# ADC_IN.net
KiCad netlist of a schematic drawn in Altium Designer
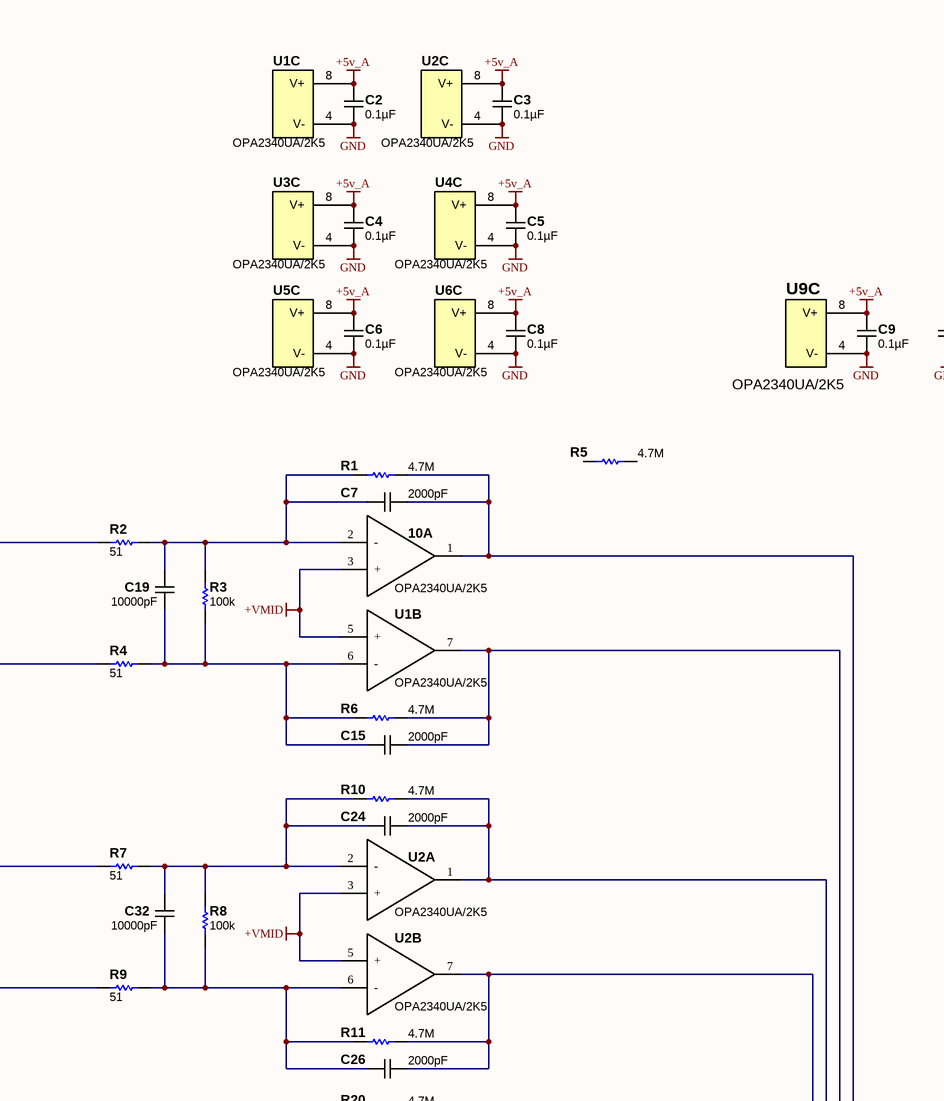
[diagram p0: ADC_IN.SchDoc, top left]
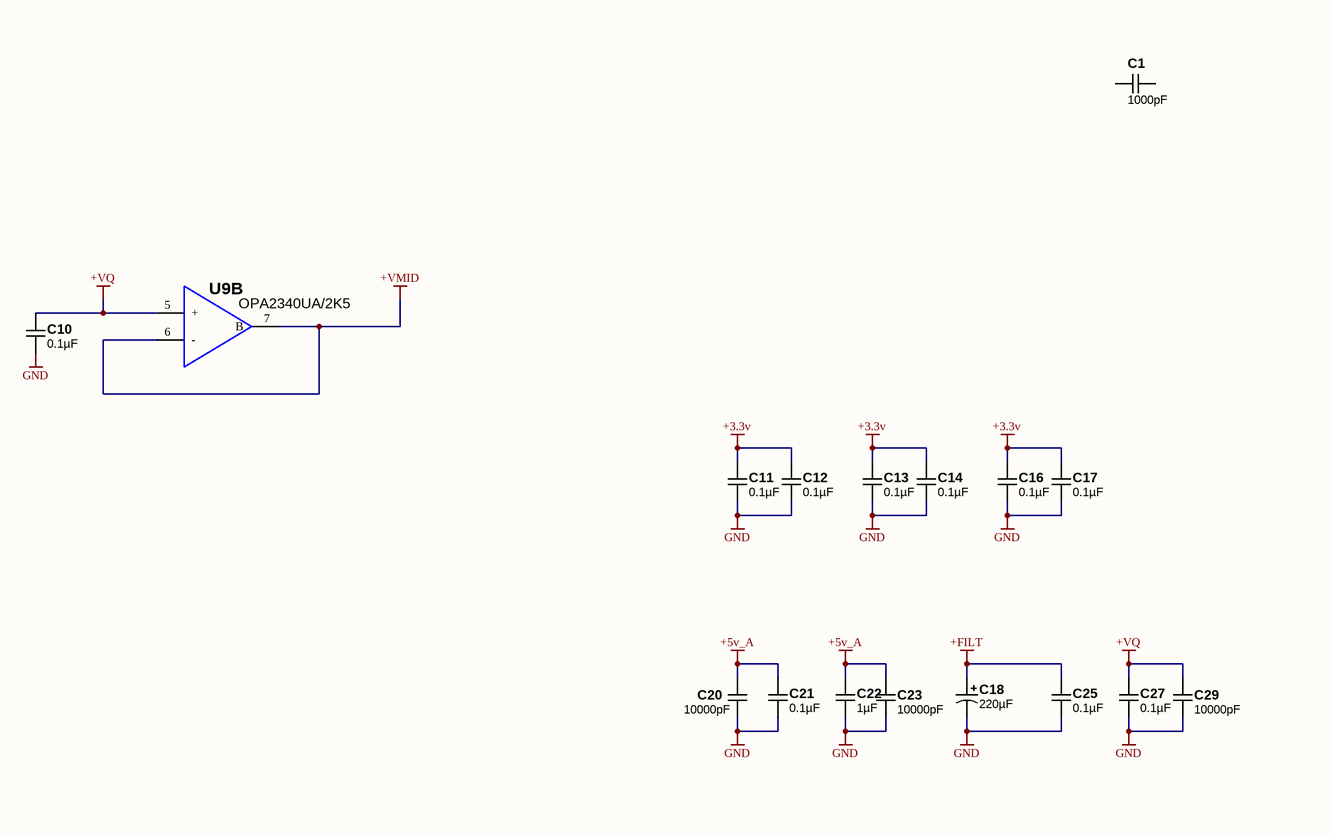
[diagram p1: ADC_IN.SchDoc, top right]
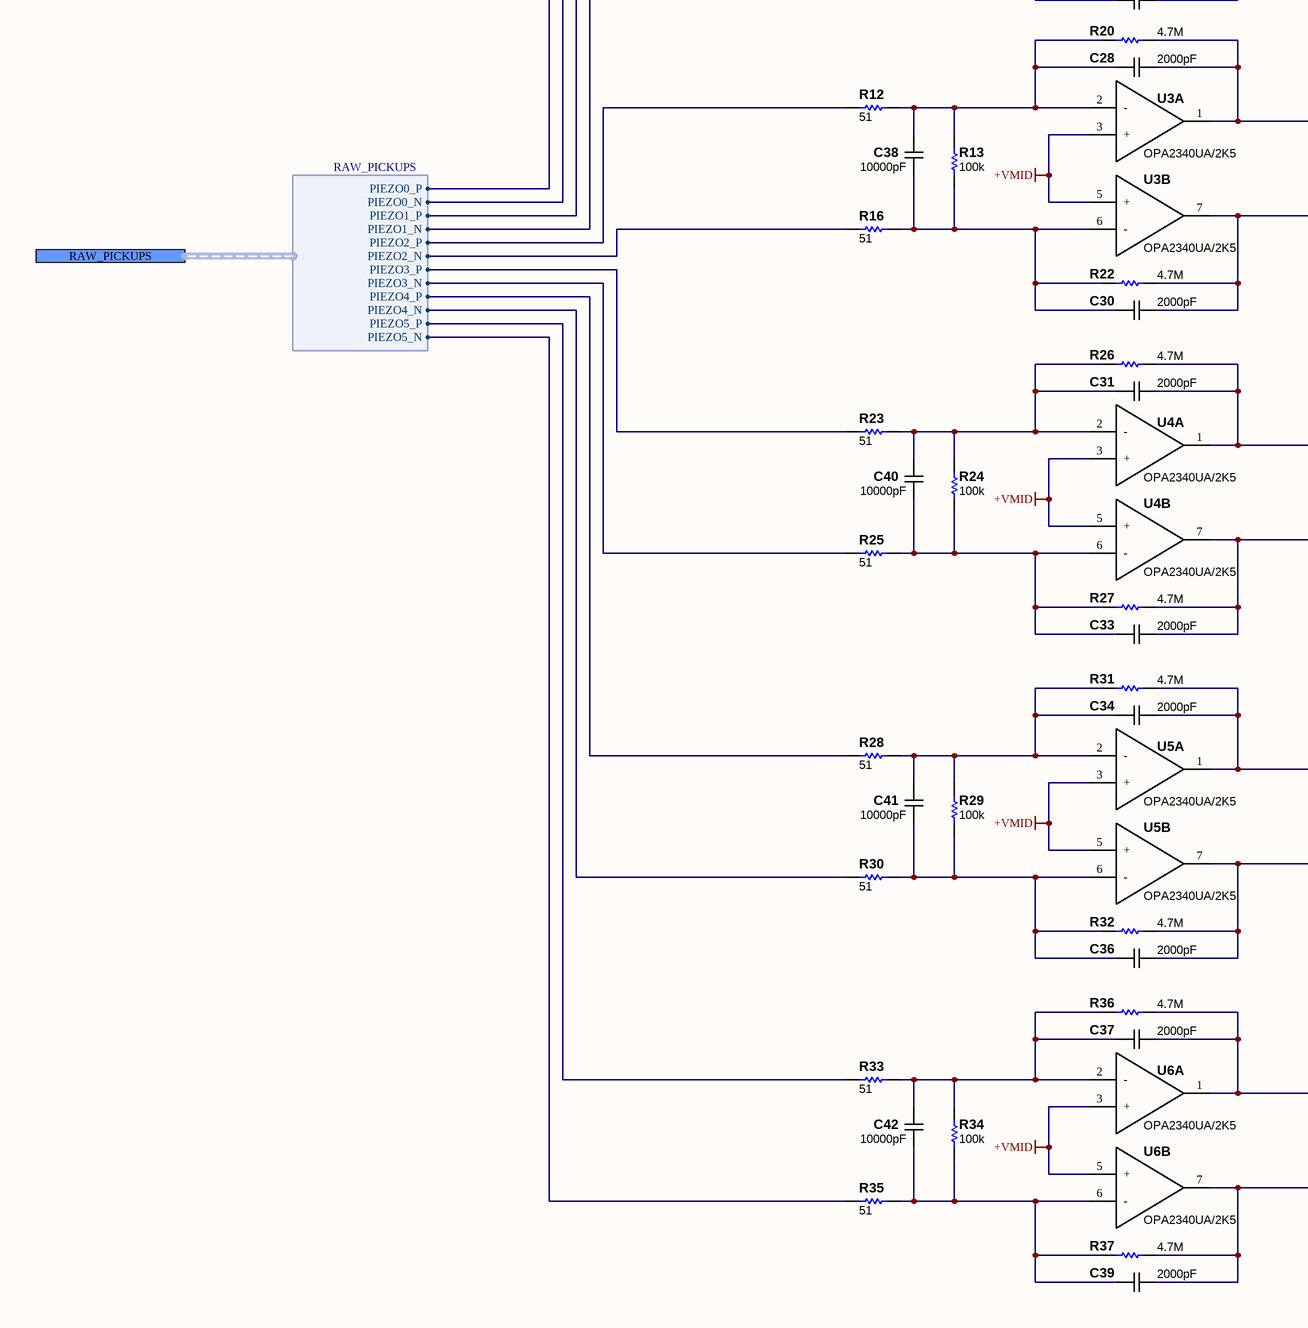
[diagram p2: ADC_IN.SchDoc, bottom left]
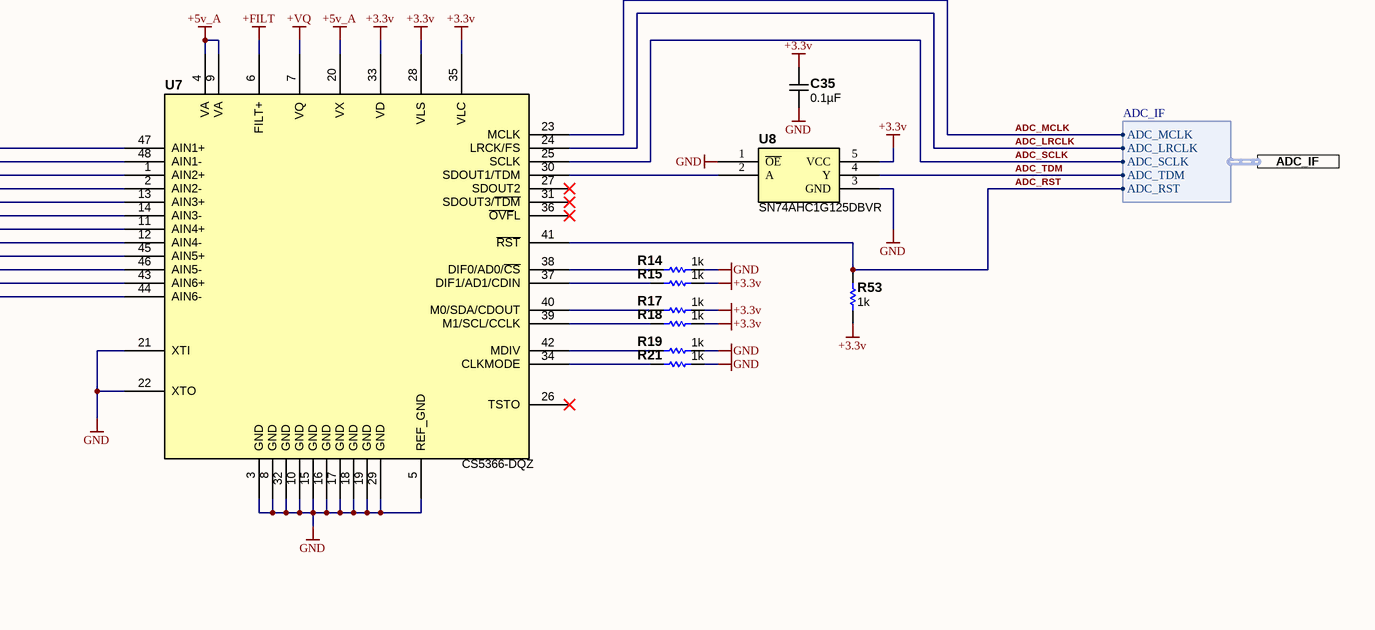
[diagram p3: ADC_IN.SchDoc, bottom right]

(export (version "E")
  (design (tool "Eeschema 10.0.6"))
  (components
    (comp (ref "10")
      (value "OPA2340UA/2K5")
      (footprint "SOIC 8")
      (description "IC OPAMP GP 5.5MHZ RRO 8SOIC")
      (fields (field (name "MANUFACTURER") "Texas Instruments"))
      (libsource (lib "") (part "OPA2340UA/2K5_1"))
    )
    (comp (ref "C1")
      (value "1000pF")
      (footprint "C0603_0.90MM_MD")
      (description "CAP CER 1000PF 50V C0G/NP0 0603")
      (fields
        (field (name "MANUFACTURER PART NUMBER") "CL10C102FB8NNNC")
        (field (name "MANUFACTURER") "Samsung Electro-Mechanics")
      )
      (libsource (lib "Capacitors - Samsung - 1%") (part "C_2P_NP"))
    )
    (comp (ref "C2")
      (value "0.1µF")
      (footprint "C0603_0.90MM_MD")
      (description "CAP CER 0.1UF 50V X7R 0603")
      (fields
        (field (name "MANUFACTURER PART NUMBER") "CGA3E2X7R1H104K080AA")
        (field (name "MANUFACTURER") "TDK Corporation")
      )
      (libsource (lib "Capacitors - TDK- AEC-Q200") (part "C_2P_NP"))
    )
    (comp (ref "C3")
      (value "0.1µF")
      (footprint "C0603_0.90MM_MD")
      (description "CAP CER 0.1UF 50V X7R 0603")
      (fields
        (field (name "MANUFACTURER PART NUMBER") "CGA3E2X7R1H104K080AA")
        (field (name "MANUFACTURER") "TDK Corporation")
      )
      (libsource (lib "Capacitors - TDK- AEC-Q200") (part "C_2P_NP"))
    )
    (comp (ref "C4")
      (value "0.1µF")
      (footprint "C0603_0.90MM_MD")
      (description "CAP CER 0.1UF 50V X7R 0603")
      (fields
        (field (name "MANUFACTURER PART NUMBER") "CGA3E2X7R1H104K080AA")
        (field (name "MANUFACTURER") "TDK Corporation")
      )
      (libsource (lib "Capacitors - TDK- AEC-Q200") (part "C_2P_NP"))
    )
    (comp (ref "C5")
      (value "0.1µF")
      (footprint "C0603_0.90MM_MD")
      (description "CAP CER 0.1UF 50V X7R 0603")
      (fields
        (field (name "MANUFACTURER PART NUMBER") "CGA3E2X7R1H104K080AA")
        (field (name "MANUFACTURER") "TDK Corporation")
      )
      (libsource (lib "Capacitors - TDK- AEC-Q200") (part "C_2P_NP"))
    )
    (comp (ref "C6")
      (value "0.1µF")
      (footprint "C0603_0.90MM_MD")
      (description "CAP CER 0.1UF 50V X7R 0603")
      (fields
        (field (name "MANUFACTURER PART NUMBER") "CGA3E2X7R1H104K080AA")
        (field (name "MANUFACTURER") "TDK Corporation")
      )
      (libsource (lib "Capacitors - TDK- AEC-Q200") (part "C_2P_NP"))
    )
    (comp (ref "C7")
      (value "2000pF")
      (footprint "C0603_MD")
      (description "CAP CER 2000PF 50V 5% NP0 0603")
      (fields
        (field (name "MANUFACTURER PART NUMBER") "GRM1885C1H202JA01D")
        (field (name "MANUFACTURER") "Murata Electronics North America")
      )
      (libsource (lib "Capacitors") (part "C_2P_NP"))
    )
    (comp (ref "C8")
      (value "0.1µF")
      (footprint "C0603_0.90MM_MD")
      (description "CAP CER 0.1UF 50V X7R 0603")
      (fields
        (field (name "MANUFACTURER PART NUMBER") "CGA3E2X7R1H104K080AA")
        (field (name "MANUFACTURER") "TDK Corporation")
      )
      (libsource (lib "Capacitors - TDK- AEC-Q200") (part "C_2P_NP"))
    )
    (comp (ref "C9")
      (value "0.1µF")
      (footprint "C0603_0.90MM_MD")
      (description "CAP CER 0.1UF 50V X7R 0603")
      (fields
        (field (name "MANUFACTURER PART NUMBER") "CGA3E2X7R1H104K080AA")
        (field (name "MANUFACTURER") "TDK Corporation")
      )
      (libsource (lib "Capacitors - TDK- AEC-Q200") (part "C_2P_NP"))
    )
    (comp (ref "C10")
      (value "0.1µF")
      (footprint "C0603_0.90MM_MD")
      (description "CAP CER 0.1UF 50V X7R 0603")
      (fields
        (field (name "MANUFACTURER PART NUMBER") "CGA3E2X7R1H104K080AA")
        (field (name "MANUFACTURER") "TDK Corporation")
      )
      (libsource (lib "Capacitors - TDK- AEC-Q200") (part "C_2P_NP"))
    )
    (comp (ref "C11")
      (value "0.1µF")
      (footprint "C0603_0.90MM_MD")
      (description "CAP CER 0.1UF 50V X7R 0603")
      (fields
        (field (name "MANUFACTURER PART NUMBER") "CGA3E2X7R1H104K080AA")
        (field (name "MANUFACTURER") "TDK Corporation")
      )
      (libsource (lib "Capacitors - TDK- AEC-Q200") (part "C_2P_NP"))
    )
    (comp (ref "C12")
      (value "0.1µF")
      (footprint "C0603_0.90MM_MD")
      (description "CAP CER 0.1UF 50V X7R 0603")
      (fields
        (field (name "MANUFACTURER PART NUMBER") "CGA3E2X7R1H104K080AA")
        (field (name "MANUFACTURER") "TDK Corporation")
      )
      (libsource (lib "Capacitors - TDK- AEC-Q200") (part "C_2P_NP"))
    )
    (comp (ref "C13")
      (value "0.1µF")
      (footprint "C0603_0.90MM_MD")
      (description "CAP CER 0.1UF 50V X7R 0603")
      (fields
        (field (name "MANUFACTURER PART NUMBER") "CGA3E2X7R1H104K080AA")
        (field (name "MANUFACTURER") "TDK Corporation")
      )
      (libsource (lib "Capacitors - TDK- AEC-Q200") (part "C_2P_NP"))
    )
    (comp (ref "C14")
      (value "0.1µF")
      (footprint "C0603_0.90MM_MD")
      (description "CAP CER 0.1UF 50V X7R 0603")
      (fields
        (field (name "MANUFACTURER PART NUMBER") "CGA3E2X7R1H104K080AA")
        (field (name "MANUFACTURER") "TDK Corporation")
      )
      (libsource (lib "Capacitors - TDK- AEC-Q200") (part "C_2P_NP"))
    )
    (comp (ref "C15")
      (value "2000pF")
      (footprint "C0603_MD")
      (description "CAP CER 2000PF 50V 5% NP0 0603")
      (fields
        (field (name "MANUFACTURER PART NUMBER") "GRM1885C1H202JA01D")
        (field (name "MANUFACTURER") "Murata Electronics North America")
      )
      (libsource (lib "Capacitors") (part "C_2P_NP"))
    )
    (comp (ref "C16")
      (value "0.1µF")
      (footprint "C0603_0.90MM_MD")
      (description "CAP CER 0.1UF 50V X7R 0603")
      (fields
        (field (name "MANUFACTURER PART NUMBER") "CGA3E2X7R1H104K080AA")
        (field (name "MANUFACTURER") "TDK Corporation")
      )
      (libsource (lib "Capacitors - TDK- AEC-Q200") (part "C_2P_NP"))
    )
    (comp (ref "C17")
      (value "0.1µF")
      (footprint "C0603_0.90MM_MD")
      (description "CAP CER 0.1UF 50V X7R 0603")
      (fields
        (field (name "MANUFACTURER PART NUMBER") "CGA3E2X7R1H104K080AA")
        (field (name "MANUFACTURER") "TDK Corporation")
      )
      (libsource (lib "Capacitors - TDK- AEC-Q200") (part "C_2P_NP"))
    )
    (comp (ref "C18")
      (value "220µF")
      (footprint "C_TANT_D_HD")
      (description "CAP TANT 220UF 10V 10% 2917")
      (fields
        (field (name "MANUFACTURER PART NUMBER") "T495D227K010ATE125")
        (field (name "MANUFACTURER") "Kemet")
      )
      (libsource (lib "Capacitors") (part "C_2P_P"))
    )
    (comp (ref "C19")
      (value "10000pF")
      (footprint "C0603_0.90MM_MD")
      (description "CAP CER 10000PF 50V X7R 0603")
      (fields
        (field (name "MANUFACTURER PART NUMBER") "CGA3E2X7R1H103K080AA")
        (field (name "MANUFACTURER") "TDK Corporation")
      )
      (libsource (lib "Capacitors - TDK- AEC-Q200") (part "C_2P_NP"))
    )
    (comp (ref "C20")
      (value "10000pF")
      (footprint "C0603_0.90MM_MD")
      (description "CAP CER 10000PF 50V X7R 0603")
      (fields
        (field (name "MANUFACTURER PART NUMBER") "CGA3E2X7R1H103K080AA")
        (field (name "MANUFACTURER") "TDK Corporation")
      )
      (libsource (lib "Capacitors - TDK- AEC-Q200") (part "C_2P_NP"))
    )
    (comp (ref "C21")
      (value "0.1µF")
      (footprint "C0603_0.90MM_MD")
      (description "CAP CER 0.1UF 50V X7R 0603")
      (fields
        (field (name "MANUFACTURER PART NUMBER") "CGA3E2X7R1H104K080AA")
        (field (name "MANUFACTURER") "TDK Corporation")
      )
      (libsource (lib "Capacitors - TDK- AEC-Q200") (part "C_2P_NP"))
    )
    (comp (ref "C22")
      (value "1µF")
      (footprint "C0603_0.90MM_MD")
      (description "CAP CER 1UF 25V X7R 0603")
      (fields
        (field (name "MANUFACTURER PART NUMBER") "CGA3E1X7R1E105K080AC")
        (field (name "MANUFACTURER") "TDK Corporation")
      )
      (libsource (lib "Capacitors - TDK- AEC-Q200") (part "C_2P_NP"))
    )
    (comp (ref "C23")
      (value "10000pF")
      (footprint "C0603_0.90MM_MD")
      (description "CAP CER 10000PF 50V X7R 0603")
      (fields
        (field (name "MANUFACTURER PART NUMBER") "CGA3E2X7R1H103K080AA")
        (field (name "MANUFACTURER") "TDK Corporation")
      )
      (libsource (lib "Capacitors - TDK- AEC-Q200") (part "C_2P_NP"))
    )
    (comp (ref "C24")
      (value "2000pF")
      (footprint "C0603_MD")
      (description "CAP CER 2000PF 50V 5% NP0 0603")
      (fields
        (field (name "MANUFACTURER PART NUMBER") "GRM1885C1H202JA01D")
        (field (name "MANUFACTURER") "Murata Electronics North America")
      )
      (libsource (lib "Capacitors") (part "C_2P_NP"))
    )
    (comp (ref "C25")
      (value "0.1µF")
      (footprint "C0603_0.90MM_MD")
      (description "CAP CER 0.1UF 50V X7R 0603")
      (fields
        (field (name "MANUFACTURER PART NUMBER") "CGA3E2X7R1H104K080AA")
        (field (name "MANUFACTURER") "TDK Corporation")
      )
      (libsource (lib "Capacitors - TDK- AEC-Q200") (part "C_2P_NP"))
    )
    (comp (ref "C26")
      (value "2000pF")
      (footprint "C0603_MD")
      (description "CAP CER 2000PF 50V 5% NP0 0603")
      (fields
        (field (name "MANUFACTURER PART NUMBER") "GRM1885C1H202JA01D")
        (field (name "MANUFACTURER") "Murata Electronics North America")
      )
      (libsource (lib "Capacitors") (part "C_2P_NP"))
    )
    (comp (ref "C27")
      (value "0.1µF")
      (footprint "C0603_0.90MM_MD")
      (description "CAP CER 0.1UF 50V X7R 0603")
      (fields
        (field (name "MANUFACTURER PART NUMBER") "CGA3E2X7R1H104K080AA")
        (field (name "MANUFACTURER") "TDK Corporation")
      )
      (libsource (lib "Capacitors - TDK- AEC-Q200") (part "C_2P_NP"))
    )
    (comp (ref "C28")
      (value "2000pF")
      (footprint "C0603_MD")
      (description "CAP CER 2000PF 50V 5% NP0 0603")
      (fields
        (field (name "MANUFACTURER PART NUMBER") "GRM1885C1H202JA01D")
        (field (name "MANUFACTURER") "Murata Electronics North America")
      )
      (libsource (lib "Capacitors") (part "C_2P_NP"))
    )
    (comp (ref "C29")
      (value "10000pF")
      (footprint "C0603_0.90MM_MD")
      (description "CAP CER 10000PF 50V X7R 0603")
      (fields
        (field (name "MANUFACTURER PART NUMBER") "CGA3E2X7R1H103K080AA")
        (field (name "MANUFACTURER") "TDK Corporation")
      )
      (libsource (lib "Capacitors - TDK- AEC-Q200") (part "C_2P_NP"))
    )
    (comp (ref "C30")
      (value "2000pF")
      (footprint "C0603_MD")
      (description "CAP CER 2000PF 50V 5% NP0 0603")
      (fields
        (field (name "MANUFACTURER PART NUMBER") "GRM1885C1H202JA01D")
        (field (name "MANUFACTURER") "Murata Electronics North America")
      )
      (libsource (lib "Capacitors") (part "C_2P_NP"))
    )
    (comp (ref "C31")
      (value "2000pF")
      (footprint "C0603_MD")
      (description "CAP CER 2000PF 50V 5% NP0 0603")
      (fields
        (field (name "MANUFACTURER PART NUMBER") "GRM1885C1H202JA01D")
        (field (name "MANUFACTURER") "Murata Electronics North America")
      )
      (libsource (lib "Capacitors") (part "C_2P_NP"))
    )
    (comp (ref "C32")
      (value "10000pF")
      (footprint "C0603_0.90MM_MD")
      (description "CAP CER 10000PF 50V X7R 0603")
      (fields
        (field (name "MANUFACTURER PART NUMBER") "CGA3E2X7R1H103K080AA")
        (field (name "MANUFACTURER") "TDK Corporation")
      )
      (libsource (lib "Capacitors - TDK- AEC-Q200") (part "C_2P_NP"))
    )
    (comp (ref "C33")
      (value "2000pF")
      (footprint "C0603_MD")
      (description "CAP CER 2000PF 50V 5% NP0 0603")
      (fields
        (field (name "MANUFACTURER PART NUMBER") "GRM1885C1H202JA01D")
        (field (name "MANUFACTURER") "Murata Electronics North America")
      )
      (libsource (lib "Capacitors") (part "C_2P_NP"))
    )
    (comp (ref "C34")
      (value "2000pF")
      (footprint "C0603_MD")
      (description "CAP CER 2000PF 50V 5% NP0 0603")
      (fields
        (field (name "MANUFACTURER PART NUMBER") "GRM1885C1H202JA01D")
        (field (name "MANUFACTURER") "Murata Electronics North America")
      )
      (libsource (lib "Capacitors") (part "C_2P_NP"))
    )
    (comp (ref "C35")
      (value "0.1µF")
      (footprint "C0603_0.90MM_MD")
      (description "CAP CER 0.1UF 50V X7R 0603")
      (fields
        (field (name "MANUFACTURER PART NUMBER") "CGA3E2X7R1H104K080AA")
        (field (name "MANUFACTURER") "TDK Corporation")
      )
      (libsource (lib "Capacitors - TDK- AEC-Q200") (part "C_2P_NP"))
    )
    (comp (ref "C36")
      (value "2000pF")
      (footprint "C0603_MD")
      (description "CAP CER 2000PF 50V 5% NP0 0603")
      (fields
        (field (name "MANUFACTURER PART NUMBER") "GRM1885C1H202JA01D")
        (field (name "MANUFACTURER") "Murata Electronics North America")
      )
      (libsource (lib "Capacitors") (part "C_2P_NP"))
    )
    (comp (ref "C37")
      (value "2000pF")
      (footprint "C0603_MD")
      (description "CAP CER 2000PF 50V 5% NP0 0603")
      (fields
        (field (name "MANUFACTURER PART NUMBER") "GRM1885C1H202JA01D")
        (field (name "MANUFACTURER") "Murata Electronics North America")
      )
      (libsource (lib "Capacitors") (part "C_2P_NP"))
    )
    (comp (ref "C38")
      (value "10000pF")
      (footprint "C0603_0.90MM_MD")
      (description "CAP CER 10000PF 50V X7R 0603")
      (fields
        (field (name "MANUFACTURER PART NUMBER") "CGA3E2X7R1H103K080AA")
        (field (name "MANUFACTURER") "TDK Corporation")
      )
      (libsource (lib "Capacitors - TDK- AEC-Q200") (part "C_2P_NP"))
    )
    (comp (ref "C39")
      (value "2000pF")
      (footprint "C0603_MD")
      (description "CAP CER 2000PF 50V 5% NP0 0603")
      (fields
        (field (name "MANUFACTURER PART NUMBER") "GRM1885C1H202JA01D")
        (field (name "MANUFACTURER") "Murata Electronics North America")
      )
      (libsource (lib "Capacitors") (part "C_2P_NP"))
    )
    (comp (ref "C40")
      (value "10000pF")
      (footprint "C0603_0.90MM_MD")
      (description "CAP CER 10000PF 50V X7R 0603")
      (fields
        (field (name "MANUFACTURER PART NUMBER") "CGA3E2X7R1H103K080AA")
        (field (name "MANUFACTURER") "TDK Corporation")
      )
      (libsource (lib "Capacitors - TDK- AEC-Q200") (part "C_2P_NP"))
    )
    (comp (ref "C41")
      (value "10000pF")
      (footprint "C0603_0.90MM_MD")
      (description "CAP CER 10000PF 50V X7R 0603")
      (fields
        (field (name "MANUFACTURER PART NUMBER") "CGA3E2X7R1H103K080AA")
        (field (name "MANUFACTURER") "TDK Corporation")
      )
      (libsource (lib "Capacitors - TDK- AEC-Q200") (part "C_2P_NP"))
    )
    (comp (ref "C42")
      (value "10000pF")
      (footprint "C0603_0.90MM_MD")
      (description "CAP CER 10000PF 50V X7R 0603")
      (fields
        (field (name "MANUFACTURER PART NUMBER") "CGA3E2X7R1H103K080AA")
        (field (name "MANUFACTURER") "TDK Corporation")
      )
      (libsource (lib "Capacitors - TDK- AEC-Q200") (part "C_2P_NP"))
    )
    (comp (ref "R1")
      (value "4.7M")
      (footprint "R0603_MD")
      (description "RES SMD 4.7M OHM 1% 1/10W 0603")
      (fields
        (field (name "MANUFACTURER") "Yageo")
        (field (name "MANUFACTURER PART NUMBER") "RC0603FR-074M7L")
      )
      (libsource (lib "eResistors") (part "RC0603FR-074M7L"))
    )
    (comp (ref "R2")
      (value "51")
      (footprint "R0603_MD")
      (description "RES 51 OHM 1/10W 1% 0603 SMD")
      (fields
        (field (name "MANUFACTURER PART NUMBER") "ERJ-3EKF51R0V")
        (field (name "MANUFACTURER") "Panasonic Electronic Components")
      )
      (libsource (lib "Resistors") (part "R_2P"))
    )
    (comp (ref "R3")
      (value "100k")
      (footprint "R0603_MD")
      (description "RES 100K OHM 1/10W 1% 0603 SMD")
      (fields
        (field (name "MANUFACTURER PART NUMBER") "ERJ-3EKF1003V")
        (field (name "MANUFACTURER") "Panasonic Electronic Components")
      )
      (libsource (lib "Resistors") (part "R_2P"))
    )
    (comp (ref "R4")
      (value "51")
      (footprint "R0603_MD")
      (description "RES 51 OHM 1/10W 1% 0603 SMD")
      (fields
        (field (name "MANUFACTURER PART NUMBER") "ERJ-3EKF51R0V")
        (field (name "MANUFACTURER") "Panasonic Electronic Components")
      )
      (libsource (lib "Resistors") (part "R_2P"))
    )
    (comp (ref "R5")
      (value "4.7M")
      (footprint "R0603_MD")
      (description "RES SMD 4.7M OHM 1% 1/10W 0603")
      (fields
        (field (name "MANUFACTURER") "Yageo")
        (field (name "MANUFACTURER PART NUMBER") "RC0603FR-074M7L")
      )
      (libsource (lib "eResistors") (part "RC0603FR-074M7L"))
    )
    (comp (ref "R6")
      (value "4.7M")
      (footprint "R0603_MD")
      (description "RES SMD 4.7M OHM 1% 1/10W 0603")
      (fields
        (field (name "MANUFACTURER") "Yageo")
        (field (name "MANUFACTURER PART NUMBER") "RC0603FR-074M7L")
      )
      (libsource (lib "eResistors") (part "RC0603FR-074M7L"))
    )
    (comp (ref "R7")
      (value "51")
      (footprint "R0603_MD")
      (description "RES 51 OHM 1/10W 1% 0603 SMD")
      (fields
        (field (name "MANUFACTURER PART NUMBER") "ERJ-3EKF51R0V")
        (field (name "MANUFACTURER") "Panasonic Electronic Components")
      )
      (libsource (lib "Resistors") (part "R_2P"))
    )
    (comp (ref "R8")
      (value "100k")
      (footprint "R0603_MD")
      (description "RES 100K OHM 1/10W 1% 0603 SMD")
      (fields
        (field (name "MANUFACTURER PART NUMBER") "ERJ-3EKF1003V")
        (field (name "MANUFACTURER") "Panasonic Electronic Components")
      )
      (libsource (lib "Resistors") (part "R_2P"))
    )
    (comp (ref "R9")
      (value "51")
      (footprint "R0603_MD")
      (description "RES 51 OHM 1/10W 1% 0603 SMD")
      (fields
        (field (name "MANUFACTURER PART NUMBER") "ERJ-3EKF51R0V")
        (field (name "MANUFACTURER") "Panasonic Electronic Components")
      )
      (libsource (lib "Resistors") (part "R_2P"))
    )
    (comp (ref "R10")
      (value "4.7M")
      (footprint "R0603_MD")
      (description "RES SMD 4.7M OHM 1% 1/10W 0603")
      (fields
        (field (name "MANUFACTURER") "Yageo")
        (field (name "MANUFACTURER PART NUMBER") "RC0603FR-074M7L")
      )
      (libsource (lib "eResistors") (part "RC0603FR-074M7L"))
    )
    (comp (ref "R11")
      (value "4.7M")
      (footprint "R0603_MD")
      (description "RES SMD 4.7M OHM 1% 1/10W 0603")
      (fields
        (field (name "MANUFACTURER") "Yageo")
        (field (name "MANUFACTURER PART NUMBER") "RC0603FR-074M7L")
      )
      (libsource (lib "eResistors") (part "RC0603FR-074M7L"))
    )
    (comp (ref "R12")
      (value "51")
      (footprint "R0603_MD")
      (description "RES 51 OHM 1/10W 1% 0603 SMD")
      (fields
        (field (name "MANUFACTURER PART NUMBER") "ERJ-3EKF51R0V")
        (field (name "MANUFACTURER") "Panasonic Electronic Components")
      )
      (libsource (lib "Resistors") (part "R_2P"))
    )
    (comp (ref "R13")
      (value "100k")
      (footprint "R0603_MD")
      (description "RES 100K OHM 1/10W 1% 0603 SMD")
      (fields
        (field (name "MANUFACTURER PART NUMBER") "ERJ-3EKF1003V")
        (field (name "MANUFACTURER") "Panasonic Electronic Components")
      )
      (libsource (lib "Resistors") (part "R_2P"))
    )
    (comp (ref "R14")
      (value "1k")
      (footprint "R0603_MD")
      (description "RES 1K OHM 1/10W 1% 0603 SMD")
      (fields
        (field (name "MANUFACTURER PART NUMBER") "ERJ-3EKF1001V")
        (field (name "MANUFACTURER") "Panasonic Electronic Components")
      )
      (libsource (lib "Resistors") (part "R_2P"))
    )
    (comp (ref "R15")
      (value "1k")
      (footprint "R0603_MD")
      (description "RES 1K OHM 1/10W 1% 0603 SMD")
      (fields
        (field (name "MANUFACTURER PART NUMBER") "ERJ-3EKF1001V")
        (field (name "MANUFACTURER") "Panasonic Electronic Components")
      )
      (libsource (lib "Resistors") (part "R_2P"))
    )
    (comp (ref "R16")
      (value "51")
      (footprint "R0603_MD")
      (description "RES 51 OHM 1/10W 1% 0603 SMD")
      (fields
        (field (name "MANUFACTURER PART NUMBER") "ERJ-3EKF51R0V")
        (field (name "MANUFACTURER") "Panasonic Electronic Components")
      )
      (libsource (lib "Resistors") (part "R_2P"))
    )
    (comp (ref "R17")
      (value "1k")
      (footprint "R0603_MD")
      (description "RES 1K OHM 1/10W 1% 0603 SMD")
      (fields
        (field (name "MANUFACTURER PART NUMBER") "ERJ-3EKF1001V")
        (field (name "MANUFACTURER") "Panasonic Electronic Components")
      )
      (libsource (lib "Resistors") (part "R_2P"))
    )
    (comp (ref "R18")
      (value "1k")
      (footprint "R0603_MD")
      (description "RES 1K OHM 1/10W 1% 0603 SMD")
      (fields
        (field (name "MANUFACTURER PART NUMBER") "ERJ-3EKF1001V")
        (field (name "MANUFACTURER") "Panasonic Electronic Components")
      )
      (libsource (lib "Resistors") (part "R_2P"))
    )
    (comp (ref "R19")
      (value "1k")
      (footprint "R0603_MD")
      (description "RES 1K OHM 1/10W 1% 0603 SMD")
      (fields
        (field (name "MANUFACTURER PART NUMBER") "ERJ-3EKF1001V")
        (field (name "MANUFACTURER") "Panasonic Electronic Components")
      )
      (libsource (lib "Resistors") (part "R_2P"))
    )
    (comp (ref "R20")
      (value "4.7M")
      (footprint "R0603_MD")
      (description "RES SMD 4.7M OHM 1% 1/10W 0603")
      (fields
        (field (name "MANUFACTURER") "Yageo")
        (field (name "MANUFACTURER PART NUMBER") "RC0603FR-074M7L")
      )
      (libsource (lib "eResistors") (part "RC0603FR-074M7L"))
    )
    (comp (ref "R21")
      (value "1k")
      (footprint "R0603_MD")
      (description "RES 1K OHM 1/10W 1% 0603 SMD")
      (fields
        (field (name "MANUFACTURER PART NUMBER") "ERJ-3EKF1001V")
        (field (name "MANUFACTURER") "Panasonic Electronic Components")
      )
      (libsource (lib "Resistors") (part "R_2P"))
    )
    (comp (ref "R22")
      (value "4.7M")
      (footprint "R0603_MD")
      (description "RES SMD 4.7M OHM 1% 1/10W 0603")
      (fields
        (field (name "MANUFACTURER") "Yageo")
        (field (name "MANUFACTURER PART NUMBER") "RC0603FR-074M7L")
      )
      (libsource (lib "eResistors") (part "RC0603FR-074M7L"))
    )
    (comp (ref "R23")
      (value "51")
      (footprint "R0603_MD")
      (description "RES 51 OHM 1/10W 1% 0603 SMD")
      (fields
        (field (name "MANUFACTURER PART NUMBER") "ERJ-3EKF51R0V")
        (field (name "MANUFACTURER") "Panasonic Electronic Components")
      )
      (libsource (lib "Resistors") (part "R_2P"))
    )
    (comp (ref "R24")
      (value "100k")
      (footprint "R0603_MD")
      (description "RES 100K OHM 1/10W 1% 0603 SMD")
      (fields
        (field (name "MANUFACTURER PART NUMBER") "ERJ-3EKF1003V")
        (field (name "MANUFACTURER") "Panasonic Electronic Components")
      )
      (libsource (lib "Resistors") (part "R_2P"))
    )
    (comp (ref "R25")
      (value "51")
      (footprint "R0603_MD")
      (description "RES 51 OHM 1/10W 1% 0603 SMD")
      (fields
        (field (name "MANUFACTURER PART NUMBER") "ERJ-3EKF51R0V")
        (field (name "MANUFACTURER") "Panasonic Electronic Components")
      )
      (libsource (lib "Resistors") (part "R_2P"))
    )
    (comp (ref "R26")
      (value "4.7M")
      (footprint "R0603_MD")
      (description "RES SMD 4.7M OHM 1% 1/10W 0603")
      (fields
        (field (name "MANUFACTURER") "Yageo")
        (field (name "MANUFACTURER PART NUMBER") "RC0603FR-074M7L")
      )
      (libsource (lib "eResistors") (part "RC0603FR-074M7L"))
    )
    (comp (ref "R27")
      (value "4.7M")
      (footprint "R0603_MD")
      (description "RES SMD 4.7M OHM 1% 1/10W 0603")
      (fields
        (field (name "MANUFACTURER") "Yageo")
        (field (name "MANUFACTURER PART NUMBER") "RC0603FR-074M7L")
      )
      (libsource (lib "eResistors") (part "RC0603FR-074M7L"))
    )
    (comp (ref "R28")
      (value "51")
      (footprint "R0603_MD")
      (description "RES 51 OHM 1/10W 1% 0603 SMD")
      (fields
        (field (name "MANUFACTURER PART NUMBER") "ERJ-3EKF51R0V")
        (field (name "MANUFACTURER") "Panasonic Electronic Components")
      )
      (libsource (lib "Resistors") (part "R_2P"))
    )
    (comp (ref "R29")
      (value "100k")
      (footprint "R0603_MD")
      (description "RES 100K OHM 1/10W 1% 0603 SMD")
      (fields
        (field (name "MANUFACTURER PART NUMBER") "ERJ-3EKF1003V")
        (field (name "MANUFACTURER") "Panasonic Electronic Components")
      )
      (libsource (lib "Resistors") (part "R_2P"))
    )
    (comp (ref "R30")
      (value "51")
      (footprint "R0603_MD")
      (description "RES 51 OHM 1/10W 1% 0603 SMD")
      (fields
        (field (name "MANUFACTURER PART NUMBER") "ERJ-3EKF51R0V")
        (field (name "MANUFACTURER") "Panasonic Electronic Components")
      )
      (libsource (lib "Resistors") (part "R_2P"))
    )
    (comp (ref "R31")
      (value "4.7M")
      (footprint "R0603_MD")
      (description "RES SMD 4.7M OHM 1% 1/10W 0603")
      (fields
        (field (name "MANUFACTURER") "Yageo")
        (field (name "MANUFACTURER PART NUMBER") "RC0603FR-074M7L")
      )
      (libsource (lib "eResistors") (part "RC0603FR-074M7L"))
    )
    (comp (ref "R32")
      (value "4.7M")
      (footprint "R0603_MD")
      (description "RES SMD 4.7M OHM 1% 1/10W 0603")
      (fields
        (field (name "MANUFACTURER") "Yageo")
        (field (name "MANUFACTURER PART NUMBER") "RC0603FR-074M7L")
      )
      (libsource (lib "eResistors") (part "RC0603FR-074M7L"))
    )
    (comp (ref "R33")
      (value "51")
      (footprint "R0603_MD")
      (description "RES 51 OHM 1/10W 1% 0603 SMD")
      (fields
        (field (name "MANUFACTURER PART NUMBER") "ERJ-3EKF51R0V")
        (field (name "MANUFACTURER") "Panasonic Electronic Components")
      )
      (libsource (lib "Resistors") (part "R_2P"))
    )
    (comp (ref "R34")
      (value "100k")
      (footprint "R0603_MD")
      (description "RES 100K OHM 1/10W 1% 0603 SMD")
      (fields
        (field (name "MANUFACTURER PART NUMBER") "ERJ-3EKF1003V")
        (field (name "MANUFACTURER") "Panasonic Electronic Components")
      )
      (libsource (lib "Resistors") (part "R_2P"))
    )
    (comp (ref "R35")
      (value "51")
      (footprint "R0603_MD")
      (description "RES 51 OHM 1/10W 1% 0603 SMD")
      (fields
        (field (name "MANUFACTURER PART NUMBER") "ERJ-3EKF51R0V")
        (field (name "MANUFACTURER") "Panasonic Electronic Components")
      )
      (libsource (lib "Resistors") (part "R_2P"))
    )
    (comp (ref "R36")
      (value "4.7M")
      (footprint "R0603_MD")
      (description "RES SMD 4.7M OHM 1% 1/10W 0603")
      (fields
        (field (name "MANUFACTURER") "Yageo")
        (field (name "MANUFACTURER PART NUMBER") "RC0603FR-074M7L")
      )
      (libsource (lib "eResistors") (part "RC0603FR-074M7L"))
    )
    (comp (ref "R37")
      (value "4.7M")
      (footprint "R0603_MD")
      (description "RES SMD 4.7M OHM 1% 1/10W 0603")
      (fields
        (field (name "MANUFACTURER") "Yageo")
        (field (name "MANUFACTURER PART NUMBER") "RC0603FR-074M7L")
      )
      (libsource (lib "eResistors") (part "RC0603FR-074M7L"))
    )
    (comp (ref "R53")
      (value "1k")
      (footprint "R0603_MD")
      (description "RES 1K OHM 1/10W 1% 0603 SMD")
      (fields
        (field (name "MANUFACTURER PART NUMBER") "ERJ-3EKF1001V")
        (field (name "MANUFACTURER") "Panasonic Electronic Components")
      )
      (libsource (lib "Resistors") (part "R_2P"))
    )
    (comp (ref "U1")
      (value "OPA2340UA/2K5")
      (footprint "SOIC 8")
      (description "IC OPAMP GP 5.5MHZ RRO 8SOIC")
      (fields (field (name "MANUFACTURER") "Texas Instruments"))
      (libsource (lib "eOPAMP") (part "OPA2340UA/2K5"))
    )
    (comp (ref "U2")
      (value "OPA2340UA/2K5")
      (footprint "SOIC 8")
      (description "IC OPAMP GP 5.5MHZ RRO 8SOIC")
      (fields (field (name "MANUFACTURER") "Texas Instruments"))
      (libsource (lib "") (part "OPA2340UA/2K5_1"))
    )
    (comp (ref "U3")
      (value "OPA2340UA/2K5")
      (footprint "SOIC 8")
      (description "IC OPAMP GP 5.5MHZ RRO 8SOIC")
      (fields (field (name "MANUFACTURER") "Texas Instruments"))
      (libsource (lib "") (part "OPA2340UA/2K5_1"))
    )
    (comp (ref "U4")
      (value "OPA2340UA/2K5")
      (footprint "SOIC 8")
      (description "IC OPAMP GP 5.5MHZ RRO 8SOIC")
      (fields (field (name "MANUFACTURER") "Texas Instruments"))
      (libsource (lib "eOPAMP") (part "OPA2340UA/2K5"))
    )
    (comp (ref "U5")
      (value "OPA2340UA/2K5")
      (footprint "SOIC 8")
      (description "IC OPAMP GP 5.5MHZ RRO 8SOIC")
      (fields (field (name "MANUFACTURER") "Texas Instruments"))
      (libsource (lib "eOPAMP") (part "OPA2340UA/2K5"))
    )
    (comp (ref "U6")
      (value "OPA2340UA/2K5")
      (footprint "SOIC 8")
      (description "IC OPAMP GP 5.5MHZ RRO 8SOIC")
      (fields (field (name "MANUFACTURER") "Texas Instruments"))
      (libsource (lib "eOPAMP") (part "OPA2340UA/2K5"))
    )
    (comp (ref "U7")
      (value "CS5366-DQZ")
      (footprint "TSQFP50P900X900X145-48L")
      (description "Audio A/D Converter ICs 114dB 192kHz 6-Ch ADC w/TDM Interface")
      (fields (field (name "MANUFACTURER") "Cirrus Logic"))
      (libsource (lib "eIC") (part "CS5366-DQZ"))
    )
    (comp (ref "U8")
      (value "SN74AHC1G125DBVR")
      (footprint "SOT23-5")
      (description "IC BUS BUFF TRI-ST N-INV SOT235")
      (fields (field (name "MANUFACTURER") "Texas Instruments"))
      (libsource (lib "eIC") (part "SN74AHC1G125DBVR"))
    )
    (comp (ref "U9")
      (value "OPA2340UA/2K5")
      (footprint "SOIC 8")
      (description "IC OPAMP GP 5.5MHZ RRO 8SOIC")
      (fields (field (name "MANUFACTURER") "Texas Instruments"))
      (libsource (lib "eIC") (part "OPA2340UA/2K5"))
    )
  )
  (nets
    (net (code "3") (name "+3.3v") (class "Default")
      (node (ref "C11") (pin "2") (pinfunction "1_2") (pintype "passive"))
      (node (ref "C12") (pin "2") (pinfunction "1_2") (pintype "passive"))
      (node (ref "C13") (pin "2") (pinfunction "1_2") (pintype "passive"))
      (node (ref "C14") (pin "2") (pinfunction "1_2") (pintype "passive"))
      (node (ref "C16") (pin "2") (pinfunction "1_2") (pintype "passive"))
      (node (ref "C17") (pin "2") (pinfunction "1_2") (pintype "passive"))
      (node (ref "C35") (pin "2") (pinfunction "1_2") (pintype "passive"))
      (node (ref "R15") (pin "1") (pinfunction "1_1") (pintype "passive"))
      (node (ref "R17") (pin "1") (pinfunction "1_1") (pintype "passive"))
      (node (ref "R18") (pin "1") (pinfunction "1_1") (pintype "passive"))
      (node (ref "R53") (pin "1") (pinfunction "1_1") (pintype "passive"))
      (node (ref "U7") (pin "28") (pinfunction "VLS_28") (pintype "passive"))
      (node (ref "U7") (pin "33") (pinfunction "VD_33") (pintype "passive"))
      (node (ref "U7") (pin "35") (pinfunction "VLC_35") (pintype "passive"))
      (node (ref "U8") (pin "5") (pinfunction "VCC_5") (pintype "passive"))
    )
    (net (code "4") (name "+5v_A") (class "Default")
      (node (ref "C2") (pin "2") (pinfunction "1_2") (pintype "passive"))
      (node (ref "C20") (pin "2") (pinfunction "1_2") (pintype "passive"))
      (node (ref "C21") (pin "2") (pinfunction "1_2") (pintype "passive"))
      (node (ref "C22") (pin "2") (pinfunction "1_2") (pintype "passive"))
      (node (ref "C23") (pin "1") (pinfunction "1_1") (pintype "passive"))
      (node (ref "C3") (pin "2") (pinfunction "1_2") (pintype "passive"))
      (node (ref "C4") (pin "2") (pinfunction "1_2") (pintype "passive"))
      (node (ref "C5") (pin "2") (pinfunction "1_2") (pintype "passive"))
      (node (ref "C6") (pin "2") (pinfunction "1_2") (pintype "passive"))
      (node (ref "C8") (pin "2") (pinfunction "1_2") (pintype "passive"))
      (node (ref "C9") (pin "2") (pinfunction "1_2") (pintype "passive"))
      (node (ref "U1") (pin "8") (pinfunction "V+_8") (pintype "passive"))
      (node (ref "U2") (pin "8") (pinfunction "V+_8") (pintype "passive"))
      (node (ref "U3") (pin "8") (pinfunction "V+_8") (pintype "passive"))
      (node (ref "U4") (pin "8") (pinfunction "V+_8") (pintype "passive"))
      (node (ref "U5") (pin "8") (pinfunction "V+_8") (pintype "passive"))
      (node (ref "U6") (pin "8") (pinfunction "V+_8") (pintype "passive"))
      (node (ref "U7") (pin "20") (pinfunction "VX_20") (pintype "passive"))
      (node (ref "U7") (pin "4") (pinfunction "VA_4") (pintype "passive"))
      (node (ref "U7") (pin "9") (pinfunction "VA_9") (pintype "passive"))
      (node (ref "U9") (pin "8") (pinfunction "V+_8") (pintype "passive"))
    )
    (net (code "5") (name "+FILT") (class "Default")
      (node (ref "C18") (pin "1") (pinfunction "1_1") (pintype "passive"))
      (node (ref "C25") (pin "2") (pinfunction "1_2") (pintype "passive"))
      (node (ref "U7") (pin "6") (pinfunction "FILT+_6") (pintype "passive"))
    )
    (net (code "6") (name "+VMID") (class "Default")
      (node (ref "10") (pin "3") (pinfunction "+_3") (pintype "passive"))
      (node (ref "U1") (pin "5") (pinfunction "+_5") (pintype "passive"))
      (node (ref "U2") (pin "3") (pinfunction "+_3") (pintype "passive"))
      (node (ref "U2") (pin "5") (pinfunction "+_5") (pintype "passive"))
      (node (ref "U3") (pin "3") (pinfunction "+_3") (pintype "passive"))
      (node (ref "U3") (pin "5") (pinfunction "+_5") (pintype "passive"))
      (node (ref "U4") (pin "3") (pinfunction "+_3") (pintype "passive"))
      (node (ref "U4") (pin "5") (pinfunction "+_5") (pintype "passive"))
      (node (ref "U5") (pin "3") (pinfunction "+_3") (pintype "passive"))
      (node (ref "U5") (pin "5") (pinfunction "+_5") (pintype "passive"))
      (node (ref "U6") (pin "3") (pinfunction "+_3") (pintype "passive"))
      (node (ref "U6") (pin "5") (pinfunction "+_5") (pintype "passive"))
      (node (ref "U9") (pin "6") (pinfunction "-_6") (pintype "passive"))
      (node (ref "U9") (pin "7") (pinfunction "B_7") (pintype "passive"))
    )
    (net (code "7") (name "+VQ") (class "Default")
      (node (ref "C10") (pin "2") (pinfunction "1_2") (pintype "passive"))
      (node (ref "C27") (pin "2") (pinfunction "1_2") (pintype "passive"))
      (node (ref "C29") (pin "1") (pinfunction "1_1") (pintype "passive"))
      (node (ref "U7") (pin "7") (pinfunction "VQ_7") (pintype "passive"))
      (node (ref "U9") (pin "5") (pinfunction "+_5") (pintype "passive"))
    )
    (net (code "8") (name "/ADC_LRCLK") (class "Default")
      (node (ref "U7") (pin "24") (pinfunction "LRCK/FS_24") (pintype "passive"))
    )
    (net (code "9") (name "/ADC_MCLK") (class "Default")
      (node (ref "U7") (pin "23") (pinfunction "MCLK_23") (pintype "passive"))
    )
    (net (code "10") (name "/ADC_RST") (class "Default")
      (node (ref "R53") (pin "2") (pinfunction "2_2") (pintype "passive"))
      (node (ref "U7") (pin "41") (pinfunction "~{RST}_41") (pintype "passive"))
    )
    (net (code "11") (name "/ADC_SCLK") (class "Default")
      (node (ref "U7") (pin "25") (pinfunction "SCLK_25") (pintype "passive"))
    )
    (net (code "12") (name "/ADC_TDM") (class "Default")
      (node (ref "U8") (pin "4") (pinfunction "Y_4") (pintype "passive"))
    )
    (net (code "13") (name "/PIEZO0_N") (class "Default")
      (node (ref "R4") (pin "1") (pinfunction "1_1") (pintype "passive"))
    )
    (net (code "14") (name "/PIEZO0_P") (class "Default")
      (node (ref "R2") (pin "1") (pinfunction "1_1") (pintype "passive"))
    )
    (net (code "15") (name "/PIEZO1_N") (class "Default")
      (node (ref "R9") (pin "1") (pinfunction "1_1") (pintype "passive"))
    )
    (net (code "16") (name "/PIEZO1_P") (class "Default")
      (node (ref "R7") (pin "1") (pinfunction "1_1") (pintype "passive"))
    )
    (net (code "17") (name "/PIEZO2_N") (class "Default")
      (node (ref "R16") (pin "1") (pinfunction "1_1") (pintype "passive"))
    )
    (net (code "18") (name "/PIEZO2_P") (class "Default")
      (node (ref "R12") (pin "1") (pinfunction "1_1") (pintype "passive"))
    )
    (net (code "19") (name "/PIEZO3_N") (class "Default")
      (node (ref "R25") (pin "1") (pinfunction "1_1") (pintype "passive"))
    )
    (net (code "20") (name "/PIEZO3_P") (class "Default")
      (node (ref "R23") (pin "1") (pinfunction "1_1") (pintype "passive"))
    )
    (net (code "21") (name "/PIEZO4_N") (class "Default")
      (node (ref "R30") (pin "1") (pinfunction "1_1") (pintype "passive"))
    )
    (net (code "22") (name "/PIEZO4_P") (class "Default")
      (node (ref "R28") (pin "1") (pinfunction "1_1") (pintype "passive"))
    )
    (net (code "23") (name "/PIEZO5_N") (class "Default")
      (node (ref "R35") (pin "1") (pinfunction "1_1") (pintype "passive"))
    )
    (net (code "24") (name "/PIEZO5_P") (class "Default")
      (node (ref "R33") (pin "1") (pinfunction "1_1") (pintype "passive"))
    )
    (net (code "27") (name "GND") (class "Default")
      (node (ref "C10") (pin "1") (pinfunction "1_1") (pintype "passive"))
      (node (ref "C11") (pin "1") (pinfunction "1_1") (pintype "passive"))
      (node (ref "C12") (pin "1") (pinfunction "1_1") (pintype "passive"))
      (node (ref "C13") (pin "1") (pinfunction "1_1") (pintype "passive"))
      (node (ref "C14") (pin "1") (pinfunction "1_1") (pintype "passive"))
      (node (ref "C16") (pin "1") (pinfunction "1_1") (pintype "passive"))
      (node (ref "C17") (pin "1") (pinfunction "1_1") (pintype "passive"))
      (node (ref "C18") (pin "2") (pinfunction "1_2") (pintype "passive"))
      (node (ref "C2") (pin "1") (pinfunction "1_1") (pintype "passive"))
      (node (ref "C20") (pin "1") (pinfunction "1_1") (pintype "passive"))
      (node (ref "C21") (pin "1") (pinfunction "1_1") (pintype "passive"))
      (node (ref "C22") (pin "1") (pinfunction "1_1") (pintype "passive"))
      (node (ref "C23") (pin "2") (pinfunction "1_2") (pintype "passive"))
      (node (ref "C25") (pin "1") (pinfunction "1_1") (pintype "passive"))
      (node (ref "C27") (pin "1") (pinfunction "1_1") (pintype "passive"))
      (node (ref "C29") (pin "2") (pinfunction "1_2") (pintype "passive"))
      (node (ref "C3") (pin "1") (pinfunction "1_1") (pintype "passive"))
      (node (ref "C35") (pin "1") (pinfunction "1_1") (pintype "passive"))
      (node (ref "C4") (pin "1") (pinfunction "1_1") (pintype "passive"))
      (node (ref "C5") (pin "1") (pinfunction "1_1") (pintype "passive"))
      (node (ref "C6") (pin "1") (pinfunction "1_1") (pintype "passive"))
      (node (ref "C8") (pin "1") (pinfunction "1_1") (pintype "passive"))
      (node (ref "C9") (pin "1") (pinfunction "1_1") (pintype "passive"))
      (node (ref "R14") (pin "1") (pinfunction "1_1") (pintype "passive"))
      (node (ref "R19") (pin "1") (pinfunction "1_1") (pintype "passive"))
      (node (ref "R21") (pin "1") (pinfunction "1_1") (pintype "passive"))
      (node (ref "U1") (pin "4") (pinfunction "V-_4") (pintype "passive"))
      (node (ref "U2") (pin "4") (pinfunction "V-_4") (pintype "passive"))
      (node (ref "U3") (pin "4") (pinfunction "V-_4") (pintype "passive"))
      (node (ref "U4") (pin "4") (pinfunction "V-_4") (pintype "passive"))
      (node (ref "U5") (pin "4") (pinfunction "V-_4") (pintype "passive"))
      (node (ref "U6") (pin "4") (pinfunction "V-_4") (pintype "passive"))
      (node (ref "U7") (pin "10") (pinfunction "GND_10") (pintype "passive"))
      (node (ref "U7") (pin "15") (pinfunction "GND_15") (pintype "passive"))
      (node (ref "U7") (pin "16") (pinfunction "GND_16") (pintype "passive"))
      (node (ref "U7") (pin "17") (pinfunction "GND_17") (pintype "passive"))
      (node (ref "U7") (pin "18") (pinfunction "GND_18") (pintype "passive"))
      (node (ref "U7") (pin "19") (pinfunction "GND_19") (pintype "passive"))
      (node (ref "U7") (pin "21") (pinfunction "XTI_21") (pintype "passive"))
      (node (ref "U7") (pin "22") (pinfunction "XTO_22") (pintype "passive"))
      (node (ref "U7") (pin "29") (pinfunction "GND_29") (pintype "passive"))
      (node (ref "U7") (pin "3") (pinfunction "GND_3") (pintype "passive"))
      (node (ref "U7") (pin "32") (pinfunction "GND_32") (pintype "passive"))
      (node (ref "U7") (pin "5") (pinfunction "REF_GND_5") (pintype "passive"))
      (node (ref "U7") (pin "8") (pinfunction "GND_8") (pintype "passive"))
      (node (ref "U8") (pin "1") (pinfunction "~{OE}_1") (pintype "passive"))
      (node (ref "U8") (pin "3") (pinfunction "GND_3") (pintype "passive"))
      (node (ref "U9") (pin "4") (pinfunction "V-_4") (pintype "passive"))
    )
    (net (code "28") (name "Net-(10A--)") (class "Default")
      (node (ref "10") (pin "2") (pinfunction "-_2") (pintype "passive"))
      (node (ref "C19") (pin "2") (pinfunction "1_2") (pintype "passive"))
      (node (ref "C7") (pin "1") (pinfunction "1_1") (pintype "passive"))
      (node (ref "R1") (pin "1") (pinfunction "1_1") (pintype "passive"))
      (node (ref "R2") (pin "2") (pinfunction "2_2") (pintype "passive"))
      (node (ref "R3") (pin "2") (pinfunction "2_2") (pintype "passive"))
    )
    (net (code "29") (name "Net-(10A-A)") (class "Default")
      (node (ref "10") (pin "1") (pinfunction "A_1") (pintype "passive"))
      (node (ref "C7") (pin "2") (pinfunction "1_2") (pintype "passive"))
      (node (ref "R1") (pin "2") (pinfunction "2_2") (pintype "passive"))
      (node (ref "U7") (pin "43") (pinfunction "AIN6+_43") (pintype "passive"))
    )
    (net (code "30") (name "Net-(U1B--)") (class "Default")
      (node (ref "C15") (pin "1") (pinfunction "1_1") (pintype "passive"))
      (node (ref "C19") (pin "1") (pinfunction "1_1") (pintype "passive"))
      (node (ref "R3") (pin "1") (pinfunction "1_1") (pintype "passive"))
      (node (ref "R4") (pin "2") (pinfunction "2_2") (pintype "passive"))
      (node (ref "R6") (pin "1") (pinfunction "1_1") (pintype "passive"))
      (node (ref "U1") (pin "6") (pinfunction "-_6") (pintype "passive"))
    )
    (net (code "31") (name "Net-(U1B-B)") (class "Default")
      (node (ref "C15") (pin "2") (pinfunction "1_2") (pintype "passive"))
      (node (ref "R6") (pin "2") (pinfunction "2_2") (pintype "passive"))
      (node (ref "U1") (pin "7") (pinfunction "B_7") (pintype "passive"))
      (node (ref "U7") (pin "44") (pinfunction "AIN6-_44") (pintype "passive"))
    )
    (net (code "32") (name "Net-(U2A--)") (class "Default")
      (node (ref "C24") (pin "1") (pinfunction "1_1") (pintype "passive"))
      (node (ref "C32") (pin "2") (pinfunction "1_2") (pintype "passive"))
      (node (ref "R10") (pin "1") (pinfunction "1_1") (pintype "passive"))
      (node (ref "R7") (pin "2") (pinfunction "2_2") (pintype "passive"))
      (node (ref "R8") (pin "2") (pinfunction "2_2") (pintype "passive"))
      (node (ref "U2") (pin "2") (pinfunction "-_2") (pintype "passive"))
    )
    (net (code "33") (name "Net-(U2A-A)") (class "Default")
      (node (ref "C24") (pin "2") (pinfunction "1_2") (pintype "passive"))
      (node (ref "R10") (pin "2") (pinfunction "2_2") (pintype "passive"))
      (node (ref "U2") (pin "1") (pinfunction "A_1") (pintype "passive"))
      (node (ref "U7") (pin "45") (pinfunction "AIN5+_45") (pintype "passive"))
    )
    (net (code "34") (name "Net-(U2B--)") (class "Default")
      (node (ref "C26") (pin "1") (pinfunction "1_1") (pintype "passive"))
      (node (ref "C32") (pin "1") (pinfunction "1_1") (pintype "passive"))
      (node (ref "R11") (pin "1") (pinfunction "1_1") (pintype "passive"))
      (node (ref "R8") (pin "1") (pinfunction "1_1") (pintype "passive"))
      (node (ref "R9") (pin "2") (pinfunction "2_2") (pintype "passive"))
      (node (ref "U2") (pin "6") (pinfunction "-_6") (pintype "passive"))
    )
    (net (code "35") (name "Net-(U2B-B)") (class "Default")
      (node (ref "C26") (pin "2") (pinfunction "1_2") (pintype "passive"))
      (node (ref "R11") (pin "2") (pinfunction "2_2") (pintype "passive"))
      (node (ref "U2") (pin "7") (pinfunction "B_7") (pintype "passive"))
      (node (ref "U7") (pin "46") (pinfunction "AIN5-_46") (pintype "passive"))
    )
    (net (code "36") (name "Net-(U3A--)") (class "Default")
      (node (ref "C28") (pin "1") (pinfunction "1_1") (pintype "passive"))
      (node (ref "C38") (pin "2") (pinfunction "1_2") (pintype "passive"))
      (node (ref "R12") (pin "2") (pinfunction "2_2") (pintype "passive"))
      (node (ref "R13") (pin "2") (pinfunction "2_2") (pintype "passive"))
      (node (ref "R20") (pin "1") (pinfunction "1_1") (pintype "passive"))
      (node (ref "U3") (pin "2") (pinfunction "-_2") (pintype "passive"))
    )
    (net (code "37") (name "Net-(U3A-A)") (class "Default")
      (node (ref "C28") (pin "2") (pinfunction "1_2") (pintype "passive"))
      (node (ref "R20") (pin "2") (pinfunction "2_2") (pintype "passive"))
      (node (ref "U3") (pin "1") (pinfunction "A_1") (pintype "passive"))
      (node (ref "U7") (pin "47") (pinfunction "AIN1+_47") (pintype "passive"))
    )
    (net (code "38") (name "Net-(U3B--)") (class "Default")
      (node (ref "C30") (pin "1") (pinfunction "1_1") (pintype "passive"))
      (node (ref "C38") (pin "1") (pinfunction "1_1") (pintype "passive"))
      (node (ref "R13") (pin "1") (pinfunction "1_1") (pintype "passive"))
      (node (ref "R16") (pin "2") (pinfunction "2_2") (pintype "passive"))
      (node (ref "R22") (pin "1") (pinfunction "1_1") (pintype "passive"))
      (node (ref "U3") (pin "6") (pinfunction "-_6") (pintype "passive"))
    )
    (net (code "39") (name "Net-(U3B-B)") (class "Default")
      (node (ref "C30") (pin "2") (pinfunction "1_2") (pintype "passive"))
      (node (ref "R22") (pin "2") (pinfunction "2_2") (pintype "passive"))
      (node (ref "U3") (pin "7") (pinfunction "B_7") (pintype "passive"))
      (node (ref "U7") (pin "48") (pinfunction "AIN1-_48") (pintype "passive"))
    )
    (net (code "40") (name "Net-(U4A--)") (class "Default")
      (node (ref "C31") (pin "1") (pinfunction "1_1") (pintype "passive"))
      (node (ref "C40") (pin "2") (pinfunction "1_2") (pintype "passive"))
      (node (ref "R23") (pin "2") (pinfunction "2_2") (pintype "passive"))
      (node (ref "R24") (pin "2") (pinfunction "2_2") (pintype "passive"))
      (node (ref "R26") (pin "1") (pinfunction "1_1") (pintype "passive"))
      (node (ref "U4") (pin "2") (pinfunction "-_2") (pintype "passive"))
    )
    (net (code "41") (name "Net-(U4A-A)") (class "Default")
      (node (ref "C31") (pin "2") (pinfunction "1_2") (pintype "passive"))
      (node (ref "R26") (pin "2") (pinfunction "2_2") (pintype "passive"))
      (node (ref "U4") (pin "1") (pinfunction "A_1") (pintype "passive"))
      (node (ref "U7") (pin "1") (pinfunction "AIN2+_1") (pintype "passive"))
    )
    (net (code "42") (name "Net-(U4B--)") (class "Default")
      (node (ref "C33") (pin "1") (pinfunction "1_1") (pintype "passive"))
      (node (ref "C40") (pin "1") (pinfunction "1_1") (pintype "passive"))
      (node (ref "R24") (pin "1") (pinfunction "1_1") (pintype "passive"))
      (node (ref "R25") (pin "2") (pinfunction "2_2") (pintype "passive"))
      (node (ref "R27") (pin "1") (pinfunction "1_1") (pintype "passive"))
      (node (ref "U4") (pin "6") (pinfunction "-_6") (pintype "passive"))
    )
    (net (code "43") (name "Net-(U4B-B)") (class "Default")
      (node (ref "C33") (pin "2") (pinfunction "1_2") (pintype "passive"))
      (node (ref "R27") (pin "2") (pinfunction "2_2") (pintype "passive"))
      (node (ref "U4") (pin "7") (pinfunction "B_7") (pintype "passive"))
      (node (ref "U7") (pin "2") (pinfunction "AIN2-_2") (pintype "passive"))
    )
    (net (code "44") (name "Net-(U5A--)") (class "Default")
      (node (ref "C34") (pin "1") (pinfunction "1_1") (pintype "passive"))
      (node (ref "C41") (pin "2") (pinfunction "1_2") (pintype "passive"))
      (node (ref "R28") (pin "2") (pinfunction "2_2") (pintype "passive"))
      (node (ref "R29") (pin "2") (pinfunction "2_2") (pintype "passive"))
      (node (ref "R31") (pin "1") (pinfunction "1_1") (pintype "passive"))
      (node (ref "U5") (pin "2") (pinfunction "-_2") (pintype "passive"))
    )
    (net (code "45") (name "Net-(U5A-A)") (class "Default")
      (node (ref "C34") (pin "2") (pinfunction "1_2") (pintype "passive"))
      (node (ref "R31") (pin "2") (pinfunction "2_2") (pintype "passive"))
      (node (ref "U5") (pin "1") (pinfunction "A_1") (pintype "passive"))
      (node (ref "U7") (pin "11") (pinfunction "AIN4+_11") (pintype "passive"))
    )
    (net (code "46") (name "Net-(U5B--)") (class "Default")
      (node (ref "C36") (pin "1") (pinfunction "1_1") (pintype "passive"))
      (node (ref "C41") (pin "1") (pinfunction "1_1") (pintype "passive"))
      (node (ref "R29") (pin "1") (pinfunction "1_1") (pintype "passive"))
      (node (ref "R30") (pin "2") (pinfunction "2_2") (pintype "passive"))
      (node (ref "R32") (pin "1") (pinfunction "1_1") (pintype "passive"))
      (node (ref "U5") (pin "6") (pinfunction "-_6") (pintype "passive"))
    )
    (net (code "47") (name "Net-(U5B-B)") (class "Default")
      (node (ref "C36") (pin "2") (pinfunction "1_2") (pintype "passive"))
      (node (ref "R32") (pin "2") (pinfunction "2_2") (pintype "passive"))
      (node (ref "U5") (pin "7") (pinfunction "B_7") (pintype "passive"))
      (node (ref "U7") (pin "12") (pinfunction "AIN4-_12") (pintype "passive"))
    )
    (net (code "48") (name "Net-(U6A--)") (class "Default")
      (node (ref "C37") (pin "1") (pinfunction "1_1") (pintype "passive"))
      (node (ref "C42") (pin "2") (pinfunction "1_2") (pintype "passive"))
      (node (ref "R33") (pin "2") (pinfunction "2_2") (pintype "passive"))
      (node (ref "R34") (pin "2") (pinfunction "2_2") (pintype "passive"))
      (node (ref "R36") (pin "1") (pinfunction "1_1") (pintype "passive"))
      (node (ref "U6") (pin "2") (pinfunction "-_2") (pintype "passive"))
    )
    (net (code "49") (name "Net-(U6A-A)") (class "Default")
      (node (ref "C37") (pin "2") (pinfunction "1_2") (pintype "passive"))
      (node (ref "R36") (pin "2") (pinfunction "2_2") (pintype "passive"))
      (node (ref "U6") (pin "1") (pinfunction "A_1") (pintype "passive"))
      (node (ref "U7") (pin "13") (pinfunction "AIN3+_13") (pintype "passive"))
    )
    (net (code "50") (name "Net-(U6B--)") (class "Default")
      (node (ref "C39") (pin "1") (pinfunction "1_1") (pintype "passive"))
      (node (ref "C42") (pin "1") (pinfunction "1_1") (pintype "passive"))
      (node (ref "R34") (pin "1") (pinfunction "1_1") (pintype "passive"))
      (node (ref "R35") (pin "2") (pinfunction "2_2") (pintype "passive"))
      (node (ref "R37") (pin "1") (pinfunction "1_1") (pintype "passive"))
      (node (ref "U6") (pin "6") (pinfunction "-_6") (pintype "passive"))
    )
    (net (code "51") (name "Net-(U6B-B)") (class "Default")
      (node (ref "C39") (pin "2") (pinfunction "1_2") (pintype "passive"))
      (node (ref "R37") (pin "2") (pinfunction "2_2") (pintype "passive"))
      (node (ref "U6") (pin "7") (pinfunction "B_7") (pintype "passive"))
      (node (ref "U7") (pin "14") (pinfunction "AIN3-_14") (pintype "passive"))
    )
    (net (code "52") (name "Net-(U7-CLKMODE)") (class "Default")
      (node (ref "R21") (pin "2") (pinfunction "2_2") (pintype "passive"))
      (node (ref "U7") (pin "34") (pinfunction "CLKMODE_34") (pintype "passive"))
    )
    (net (code "53") (name "Net-(U7-DIF0{slash}AD0{slash}~{CS})") (class "Default")
      (node (ref "R14") (pin "2") (pinfunction "2_2") (pintype "passive"))
      (node (ref "U7") (pin "38") (pinfunction "DIF0/AD0/~{CS}_38") (pintype "passive"))
    )
    (net (code "54") (name "Net-(U7-DIF1{slash}AD1{slash}CDIN)") (class "Default")
      (node (ref "R15") (pin "2") (pinfunction "2_2") (pintype "passive"))
      (node (ref "U7") (pin "37") (pinfunction "DIF1/AD1/CDIN_37") (pintype "passive"))
    )
    (net (code "55") (name "Net-(U7-M0{slash}SDA{slash}CDOUT)") (class "Default")
      (node (ref "R17") (pin "2") (pinfunction "2_2") (pintype "passive"))
      (node (ref "U7") (pin "40") (pinfunction "M0/SDA/CDOUT_40") (pintype "passive"))
    )
    (net (code "56") (name "Net-(U7-M1{slash}SCL{slash}CCLK)") (class "Default")
      (node (ref "R18") (pin "2") (pinfunction "2_2") (pintype "passive"))
      (node (ref "U7") (pin "39") (pinfunction "M1/SCL/CCLK_39") (pintype "passive"))
    )
    (net (code "57") (name "Net-(U7-MDIV)") (class "Default")
      (node (ref "R19") (pin "2") (pinfunction "2_2") (pintype "passive"))
      (node (ref "U7") (pin "42") (pinfunction "MDIV_42") (pintype "passive"))
    )
    (net (code "58") (name "Net-(U7-SDOUT1{slash}TDM)") (class "Default")
      (node (ref "U7") (pin "30") (pinfunction "SDOUT1/TDM_30") (pintype "passive"))
      (node (ref "U8") (pin "2") (pinfunction "A_2") (pintype "passive"))
    )
    (net (code "59") (name "unconnected-(C1-1-Pad2)") (class "Default")
      (node (ref "C1") (pin "2") (pinfunction "1_2") (pintype "passive"))
    )
    (net (code "60") (name "unconnected-(C1-Pad1)") (class "Default")
      (node (ref "C1") (pin "1") (pinfunction "1_1") (pintype "passive"))
    )
    (net (code "61") (name "unconnected-(R5-Pad1)") (class "Default")
      (node (ref "R5") (pin "1") (pinfunction "1_1") (pintype "passive"))
    )
    (net (code "62") (name "unconnected-(R5-Pad2)") (class "Default")
      (node (ref "R5") (pin "2") (pinfunction "2_2") (pintype "passive"))
    )
    (net (code "63") (name "unconnected-(U7-SDOUT2-Pad27)") (class "Default")
      (node (ref "U7") (pin "27") (pinfunction "SDOUT2_27") (pintype "passive+no_connect"))
    )
    (net (code "64") (name "unconnected-(U7-SDOUT3{slash}~{TDM}-Pad31)") (class "Default")
      (node (ref "U7") (pin "31") (pinfunction "SDOUT3/~{TDM}_31") (pintype "passive+no_connect"))
    )
    (net (code "65") (name "unconnected-(U7-TSTO-Pad26)") (class "Default")
      (node (ref "U7") (pin "26") (pinfunction "TSTO_26") (pintype "passive+no_connect"))
    )
    (net (code "66") (name "unconnected-(U7-~{OVF}L-Pad36)") (class "Default")
      (node (ref "U7") (pin "36") (pinfunction "~{OVF}L_36") (pintype "passive+no_connect"))
    )
  )
)
